# Mic_to_Pi_Entire_design.net
KiCad netlist of a schematic drawn in EAGLE
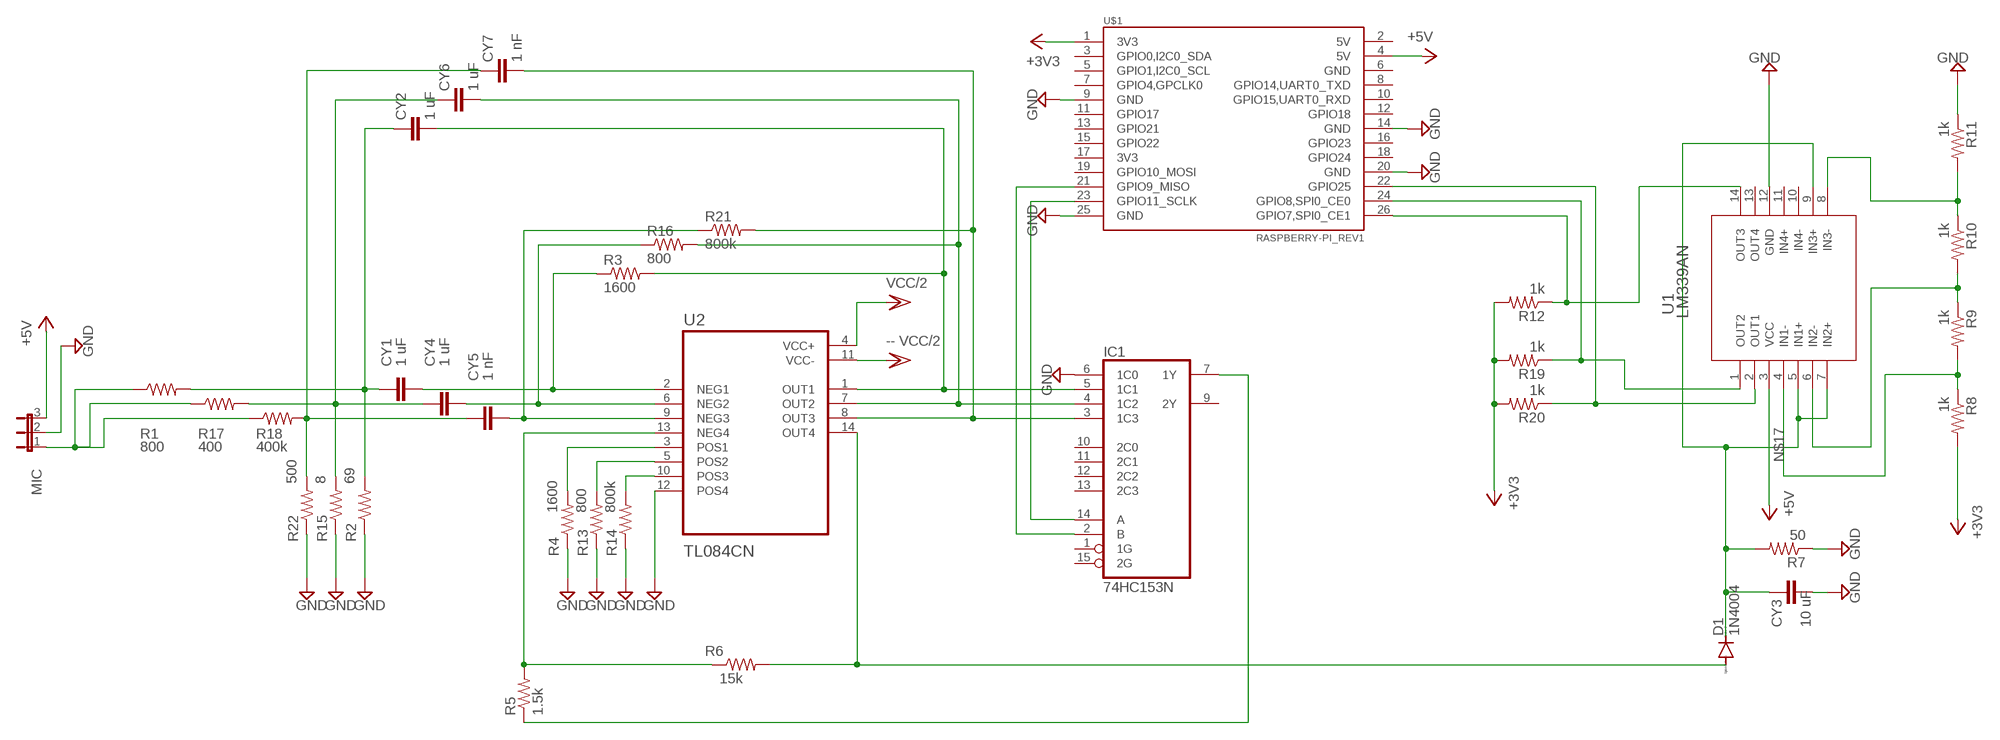
[diagram p0: schematic, sheet 1]

(export (version "E")
  (design (tool "Eeschema 10.0.6"))
  (components
    (comp (ref "CY1")
      (value "1 uF")
      (footprint "eagle-import:YC7B5")
      (libsource (lib "eagle-import") (part "CYYC7B5"))
    )
    (comp (ref "CY2")
      (value "1 uF")
      (footprint "eagle-import:YC7B5")
      (libsource (lib "eagle-import") (part "CYYC7B5"))
    )
    (comp (ref "CY3")
      (value "10 uF")
      (footprint "eagle-import:YC7B5")
      (libsource (lib "eagle-import") (part "CYYC7B5"))
    )
    (comp (ref "CY4")
      (value "1 uF")
      (footprint "eagle-import:YC7B5")
      (libsource (lib "eagle-import") (part "CYYC7B5"))
    )
    (comp (ref "CY5")
      (value "1 nF")
      (footprint "eagle-import:YC7B5")
      (libsource (lib "eagle-import") (part "CYYC7B5"))
    )
    (comp (ref "CY6")
      (value "1 uF")
      (footprint "eagle-import:YC7B5")
      (libsource (lib "eagle-import") (part "CYYC7B5"))
    )
    (comp (ref "CY7")
      (value "1 nF")
      (footprint "eagle-import:YC7B5")
      (libsource (lib "eagle-import") (part "CYYC7B5"))
    )
    (comp (ref "D1")
      (value "1N4004")
      (footprint "eagle-import:DO41-10")
      (libsource (lib "eagle-import") (part "1N4004"))
    )
    (comp (ref "IC1")
      (value "74HC153N")
      (footprint "eagle-import:DIL16")
      (libsource (lib "eagle-import") (part "74153NHC"))
    )
    (comp (ref "MIC")
      (value "JP2W")
      (footprint "eagle-import:JP2W")
      (libsource (lib "eagle-import") (part "JP2W"))
    )
    (comp (ref "R1")
      (value "800")
      (footprint "eagle-import:0204_7")
      (libsource (lib "eagle-import") (part "R-US_0204/7"))
    )
    (comp (ref "R2")
      (value "69")
      (footprint "eagle-import:0204_7")
      (libsource (lib "eagle-import") (part "R-US_0204/7"))
    )
    (comp (ref "R3")
      (value "1600")
      (footprint "eagle-import:0204_7")
      (libsource (lib "eagle-import") (part "R-US_0204/7"))
    )
    (comp (ref "R4")
      (value "1600")
      (footprint "eagle-import:0204_7")
      (libsource (lib "eagle-import") (part "R-US_0204/7"))
    )
    (comp (ref "R5")
      (value "1.5k")
      (footprint "eagle-import:0204_7")
      (libsource (lib "eagle-import") (part "R-US_0204/7"))
    )
    (comp (ref "R6")
      (value "15k")
      (footprint "eagle-import:0204_7")
      (libsource (lib "eagle-import") (part "R-US_0204/7"))
    )
    (comp (ref "R7")
      (value "50")
      (footprint "eagle-import:0204_7")
      (libsource (lib "eagle-import") (part "R-US_0204/7"))
    )
    (comp (ref "R8")
      (value "1k")
      (footprint "eagle-import:0204_7")
      (libsource (lib "eagle-import") (part "R-US_0204/7"))
    )
    (comp (ref "R9")
      (value "1k")
      (footprint "eagle-import:0207_2V")
      (libsource (lib "eagle-import") (part "R-US_0207/2V"))
    )
    (comp (ref "R10")
      (value "1k")
      (footprint "eagle-import:0207_2V")
      (libsource (lib "eagle-import") (part "R-US_0207/2V"))
    )
    (comp (ref "R11")
      (value "1k")
      (footprint "eagle-import:0207_2V")
      (libsource (lib "eagle-import") (part "R-US_0207/2V"))
    )
    (comp (ref "R12")
      (value "1k")
      (footprint "eagle-import:0207_2V")
      (libsource (lib "eagle-import") (part "R-US_0207/2V"))
    )
    (comp (ref "R13")
      (value "800")
      (footprint "eagle-import:0204_7")
      (libsource (lib "eagle-import") (part "R-US_0204/7"))
    )
    (comp (ref "R14")
      (value "800k")
      (footprint "eagle-import:0204_7")
      (libsource (lib "eagle-import") (part "R-US_0204/7"))
    )
    (comp (ref "R15")
      (value "8")
      (footprint "eagle-import:0204_7")
      (libsource (lib "eagle-import") (part "R-US_0204/7"))
    )
    (comp (ref "R16")
      (value "800")
      (footprint "eagle-import:0204_7")
      (libsource (lib "eagle-import") (part "R-US_0204/7"))
    )
    (comp (ref "R17")
      (value "400")
      (footprint "eagle-import:0204_7")
      (libsource (lib "eagle-import") (part "R-US_0204/7"))
    )
    (comp (ref "R18")
      (value "400k")
      (footprint "eagle-import:0204_7")
      (libsource (lib "eagle-import") (part "R-US_0204/7"))
    )
    (comp (ref "R19")
      (value "1k")
      (footprint "eagle-import:0204_7")
      (libsource (lib "eagle-import") (part "R-US_0204/7"))
    )
    (comp (ref "R20")
      (value "1k")
      (footprint "eagle-import:0204_7")
      (libsource (lib "eagle-import") (part "R-US_0204/7"))
    )
    (comp (ref "R21")
      (value "800k")
      (footprint "eagle-import:0204_7")
      (libsource (lib "eagle-import") (part "R-US_0204/7"))
    )
    (comp (ref "R22")
      (value "500")
      (footprint "eagle-import:0204_7")
      (libsource (lib "eagle-import") (part "R-US_0204/7"))
    )
    (comp (ref "U$1")
      (value "RASPBERRY-PI_REV1")
      (footprint "eagle-import:RASPBERRY-PI_REV1")
      (libsource (lib "eagle-import") (part "RASPBERRY-PI_REV1"))
    )
    (comp (ref "U1")
      (value "LM339AN")
      (footprint "eagle-import:PDIP14_646-06_ONS")
      (fields (field (name "COPYRIGHT") "Copyright (C) 2022 Ultra Librarian. All rights reserved."))
      (libsource (lib "eagle-import") (part "LM339AN"))
    )
    (comp (ref "U2")
      (value "TL084CN")
      (footprint "eagle-import:DIP794W45P254L1969H508Q14")
      (fields (field (name "DIGI-KEY_PART_NUMBER") "296-1784-5-ND") (field (name "MF") "Texas Instruments"))
      (libsource (lib "eagle-import") (part "TL084CN"))
    )
  )
  (nets
    (net (code "1") (name "+3V3") (class "Default")
      (node (ref "R12") (pin "2") (pinfunction "2_2") (pintype "passive"))
      (node (ref "R19") (pin "2") (pinfunction "2_2") (pintype "passive"))
      (node (ref "R20") (pin "2") (pinfunction "2_2") (pintype "passive"))
      (node (ref "R8") (pin "2") (pinfunction "2_2") (pintype "passive"))
      (node (ref "U$1") (pin "1") (pinfunction "3V3_1") (pintype "bidirectional"))
    )
    (net (code "2") (name "+5V") (class "Default")
      (node (ref "MIC") (pin "3") (pinfunction "3_3") (pintype "passive"))
      (node (ref "U$1") (pin "4") (pinfunction "5V_4") (pintype "bidirectional"))
      (node (ref "U1") (pin "3") (pinfunction "VCC_3") (pintype "power_in"))
    )
    (net (code "3") (name "-- VCC{slash}2") (class "Default")
      (node (ref "U2") (pin "11") (pinfunction "VCC-_11") (pintype "power_in"))
      (node (ref "U2") (pin "4") (pinfunction "VCC+_4") (pintype "power_in"))
    )
    (net (code "4") (name "/N$17") (class "Default")
      (node (ref "R8") (pin "1") (pinfunction "1_1") (pintype "passive"))
      (node (ref "R9") (pin "2") (pinfunction "2_2") (pintype "passive"))
      (node (ref "U1") (pin "4") (pinfunction "IN1-_4") (pintype "input"))
    )
    (net (code "5") (name "GND") (class "Default")
      (node (ref "CY3") (pin "2") (pinfunction "2_2") (pintype "passive"))
      (node (ref "IC1") (pin "6") (pinfunction "1C0_6") (pintype "input"))
      (node (ref "MIC") (pin "2") (pinfunction "2_2") (pintype "passive"))
      (node (ref "R11") (pin "1") (pinfunction "1_1") (pintype "passive"))
      (node (ref "R13") (pin "1") (pinfunction "1_1") (pintype "passive"))
      (node (ref "R14") (pin "1") (pinfunction "1_1") (pintype "passive"))
      (node (ref "R15") (pin "1") (pinfunction "1_1") (pintype "passive"))
      (node (ref "R2") (pin "1") (pinfunction "1_1") (pintype "passive"))
      (node (ref "R22") (pin "1") (pinfunction "1_1") (pintype "passive"))
      (node (ref "R4") (pin "1") (pinfunction "1_1") (pintype "passive"))
      (node (ref "R7") (pin "1") (pinfunction "1_1") (pintype "passive"))
      (node (ref "U$1") (pin "14") (pinfunction "GND_14") (pintype "bidirectional"))
      (node (ref "U$1") (pin "20") (pinfunction "GND_20") (pintype "bidirectional"))
      (node (ref "U$1") (pin "25") (pinfunction "GND_25") (pintype "bidirectional"))
      (node (ref "U$1") (pin "9") (pinfunction "GND_9") (pintype "bidirectional"))
      (node (ref "U1") (pin "12") (pinfunction "GND_12") (pintype "passive"))
      (node (ref "U2") (pin "12") (pinfunction "POS4_12") (pintype "input"))
    )
    (net (code "6") (name "Net-(CY1-Pad1)") (class "Default")
      (node (ref "CY1") (pin "1") (pinfunction "1_1") (pintype "passive"))
      (node (ref "CY2") (pin "1") (pinfunction "1_1") (pintype "passive"))
      (node (ref "R1") (pin "2") (pinfunction "2_2") (pintype "passive"))
      (node (ref "R2") (pin "2") (pinfunction "2_2") (pintype "passive"))
    )
    (net (code "7") (name "Net-(CY4-Pad1)") (class "Default")
      (node (ref "CY4") (pin "1") (pinfunction "1_1") (pintype "passive"))
      (node (ref "CY6") (pin "1") (pinfunction "1_1") (pintype "passive"))
      (node (ref "R15") (pin "2") (pinfunction "2_2") (pintype "passive"))
      (node (ref "R17") (pin "2") (pinfunction "2_2") (pintype "passive"))
    )
    (net (code "8") (name "Net-(CY5-Pad1)") (class "Default")
      (node (ref "CY5") (pin "1") (pinfunction "1_1") (pintype "passive"))
      (node (ref "CY7") (pin "1") (pinfunction "1_1") (pintype "passive"))
      (node (ref "R18") (pin "2") (pinfunction "2_2") (pintype "passive"))
      (node (ref "R22") (pin "2") (pinfunction "2_2") (pintype "passive"))
    )
    (net (code "9") (name "Net-(IC1A-1C1)") (class "Default")
      (node (ref "CY2") (pin "2") (pinfunction "2_2") (pintype "passive"))
      (node (ref "IC1") (pin "5") (pinfunction "1C1_5") (pintype "input"))
      (node (ref "R3") (pin "2") (pinfunction "2_2") (pintype "passive"))
      (node (ref "U2") (pin "1") (pinfunction "OUT1_1") (pintype "output"))
    )
    (net (code "10") (name "Net-(IC1A-1C2)") (class "Default")
      (node (ref "CY6") (pin "2") (pinfunction "2_2") (pintype "passive"))
      (node (ref "IC1") (pin "4") (pinfunction "1C2_4") (pintype "input"))
      (node (ref "R16") (pin "2") (pinfunction "2_2") (pintype "passive"))
      (node (ref "U2") (pin "7") (pinfunction "OUT2_7") (pintype "output"))
    )
    (net (code "11") (name "Net-(IC1A-1C3)") (class "Default")
      (node (ref "CY7") (pin "2") (pinfunction "2_2") (pintype "passive"))
      (node (ref "IC1") (pin "3") (pinfunction "1C3_3") (pintype "input"))
      (node (ref "R21") (pin "2") (pinfunction "2_2") (pintype "passive"))
      (node (ref "U2") (pin "8") (pinfunction "OUT3_8") (pintype "output"))
    )
    (net (code "12") (name "Net-(IC1A-1Y)") (class "Default")
      (node (ref "IC1") (pin "7") (pinfunction "1Y_7") (pintype "output"))
      (node (ref "R5") (pin "1") (pinfunction "1_1") (pintype "passive"))
    )
    (net (code "13") (name "Net-(IC1A-A)") (class "Default")
      (node (ref "IC1") (pin "14") (pinfunction "A_14") (pintype "input"))
      (node (ref "U$1") (pin "23") (pinfunction "GPIO11_SCLK_23") (pintype "bidirectional"))
    )
    (net (code "14") (name "Net-(IC1A-B)") (class "Default")
      (node (ref "IC1") (pin "2") (pinfunction "B_2") (pintype "input"))
      (node (ref "U$1") (pin "21") (pinfunction "GPIO9_MISO_21") (pintype "bidirectional"))
    )
    (net (code "15") (name "Net-(MIC-Pad1)") (class "Default")
      (node (ref "MIC") (pin "1") (pinfunction "1_1") (pintype "passive"))
      (node (ref "R1") (pin "1") (pinfunction "1_1") (pintype "passive"))
      (node (ref "R17") (pin "1") (pinfunction "1_1") (pintype "passive"))
      (node (ref "R18") (pin "1") (pinfunction "1_1") (pintype "passive"))
    )
    (net (code "16") (name "Net-(U$1-GPIO7,SPI0_CE1)") (class "Default")
      (node (ref "R12") (pin "1") (pinfunction "1_1") (pintype "passive"))
      (node (ref "U$1") (pin "26") (pinfunction "GPIO7,SPI0_CE1_26") (pintype "bidirectional"))
      (node (ref "U1") (pin "14") (pinfunction "OUT3_14") (pintype "output"))
    )
    (net (code "17") (name "Net-(U$1-GPIO8,SPI0_CE0)") (class "Default")
      (node (ref "R19") (pin "1") (pinfunction "1_1") (pintype "passive"))
      (node (ref "U$1") (pin "24") (pinfunction "GPIO8,SPI0_CE0_24") (pintype "bidirectional"))
      (node (ref "U1") (pin "1") (pinfunction "OUT2_1") (pintype "output"))
    )
    (net (code "18") (name "Net-(U$1-GPIO25)") (class "Default")
      (node (ref "R20") (pin "1") (pinfunction "1_1") (pintype "passive"))
      (node (ref "U$1") (pin "22") (pinfunction "GPIO25_22") (pintype "bidirectional"))
      (node (ref "U1") (pin "2") (pinfunction "OUT1_2") (pintype "output"))
    )
    (net (code "19") (name "Net-(U1-IN1+)") (class "Default")
      (node (ref "CY3") (pin "1") (pinfunction "1_1") (pintype "passive"))
      (node (ref "D1") (pin "C") (pinfunction "C_C") (pintype "passive"))
      (node (ref "R7") (pin "2") (pinfunction "2_2") (pintype "passive"))
      (node (ref "U1") (pin "5") (pinfunction "IN1+_5") (pintype "input"))
      (node (ref "U1") (pin "7") (pinfunction "IN2+_7") (pintype "input"))
      (node (ref "U1") (pin "9") (pinfunction "IN3+_9") (pintype "input"))
    )
    (net (code "20") (name "Net-(U1-IN2-)") (class "Default")
      (node (ref "R10") (pin "2") (pinfunction "2_2") (pintype "passive"))
      (node (ref "R9") (pin "1") (pinfunction "1_1") (pintype "passive"))
      (node (ref "U1") (pin "6") (pinfunction "IN2-_6") (pintype "input"))
    )
    (net (code "21") (name "Net-(U1-IN3-)") (class "Default")
      (node (ref "R10") (pin "1") (pinfunction "1_1") (pintype "passive"))
      (node (ref "R11") (pin "2") (pinfunction "2_2") (pintype "passive"))
      (node (ref "U1") (pin "8") (pinfunction "IN3-_8") (pintype "input"))
    )
    (net (code "22") (name "Net-(U2-NEG1)") (class "Default")
      (node (ref "CY1") (pin "2") (pinfunction "2_2") (pintype "passive"))
      (node (ref "R3") (pin "1") (pinfunction "1_1") (pintype "passive"))
      (node (ref "U2") (pin "2") (pinfunction "NEG1_2") (pintype "input"))
    )
    (net (code "23") (name "Net-(U2-NEG2)") (class "Default")
      (node (ref "CY4") (pin "2") (pinfunction "2_2") (pintype "passive"))
      (node (ref "R16") (pin "1") (pinfunction "1_1") (pintype "passive"))
      (node (ref "U2") (pin "6") (pinfunction "NEG2_6") (pintype "input"))
    )
    (net (code "24") (name "Net-(U2-NEG3)") (class "Default")
      (node (ref "CY5") (pin "2") (pinfunction "2_2") (pintype "passive"))
      (node (ref "R21") (pin "1") (pinfunction "1_1") (pintype "passive"))
      (node (ref "U2") (pin "9") (pinfunction "NEG3_9") (pintype "input"))
    )
    (net (code "25") (name "Net-(U2-NEG4)") (class "Default")
      (node (ref "R5") (pin "2") (pinfunction "2_2") (pintype "passive"))
      (node (ref "R6") (pin "1") (pinfunction "1_1") (pintype "passive"))
      (node (ref "U2") (pin "13") (pinfunction "NEG4_13") (pintype "input"))
    )
    (net (code "26") (name "Net-(U2-OUT4)") (class "Default")
      (node (ref "D1") (pin "A") (pinfunction "A_A") (pintype "passive"))
      (node (ref "R6") (pin "2") (pinfunction "2_2") (pintype "passive"))
      (node (ref "U2") (pin "14") (pinfunction "OUT4_14") (pintype "output"))
    )
    (net (code "27") (name "Net-(U2-POS1)") (class "Default")
      (node (ref "R4") (pin "2") (pinfunction "2_2") (pintype "passive"))
      (node (ref "U2") (pin "3") (pinfunction "POS1_3") (pintype "input"))
    )
    (net (code "28") (name "Net-(U2-POS2)") (class "Default")
      (node (ref "R13") (pin "2") (pinfunction "2_2") (pintype "passive"))
      (node (ref "U2") (pin "5") (pinfunction "POS2_5") (pintype "input"))
    )
    (net (code "29") (name "Net-(U2-POS3)") (class "Default")
      (node (ref "R14") (pin "2") (pinfunction "2_2") (pintype "passive"))
      (node (ref "U2") (pin "10") (pinfunction "POS3_10") (pintype "input"))
    )
    (net (code "30") (name "unconnected-(IC1A-1G-Pad1)") (class "Default")
      (node (ref "IC1") (pin "1") (pinfunction "1G_1") (pintype "input"))
    )
    (net (code "31") (name "unconnected-(IC1A-2C0-Pad10)") (class "Default")
      (node (ref "IC1") (pin "10") (pinfunction "2C0_10") (pintype "input"))
    )
    (net (code "32") (name "unconnected-(IC1A-2C1-Pad11)") (class "Default")
      (node (ref "IC1") (pin "11") (pinfunction "2C1_11") (pintype "input"))
    )
    (net (code "33") (name "unconnected-(IC1A-2C2-Pad12)") (class "Default")
      (node (ref "IC1") (pin "12") (pinfunction "2C2_12") (pintype "input"))
    )
    (net (code "34") (name "unconnected-(IC1A-2C3-Pad13)") (class "Default")
      (node (ref "IC1") (pin "13") (pinfunction "2C3_13") (pintype "input"))
    )
    (net (code "35") (name "unconnected-(IC1A-2G-Pad15)") (class "Default")
      (node (ref "IC1") (pin "15") (pinfunction "2G_15") (pintype "input"))
    )
    (net (code "36") (name "unconnected-(IC1A-2Y-Pad9)") (class "Default")
      (node (ref "IC1") (pin "9") (pinfunction "2Y_9") (pintype "output"))
    )
    (net (code "37") (name "unconnected-(U$1-3V3-Pad17)") (class "Default")
      (node (ref "U$1") (pin "17") (pinfunction "3V3_17") (pintype "bidirectional"))
    )
    (net (code "38") (name "unconnected-(U$1-5V-Pad2)") (class "Default")
      (node (ref "U$1") (pin "2") (pinfunction "5V_2") (pintype "bidirectional"))
    )
    (net (code "39") (name "unconnected-(U$1-GND-Pad6)") (class "Default")
      (node (ref "U$1") (pin "6") (pinfunction "GND_6") (pintype "bidirectional"))
    )
    (net (code "40") (name "unconnected-(U$1-GPIO0,I2C0_SDA-Pad3)") (class "Default")
      (node (ref "U$1") (pin "3") (pinfunction "GPIO0,I2C0_SDA_3") (pintype "bidirectional"))
    )
    (net (code "41") (name "unconnected-(U$1-GPIO1,I2C0_SCL-Pad5)") (class "Default")
      (node (ref "U$1") (pin "5") (pinfunction "GPIO1,I2C0_SCL_5") (pintype "bidirectional"))
    )
    (net (code "42") (name "unconnected-(U$1-GPIO4,GPCLK0-Pad7)") (class "Default")
      (node (ref "U$1") (pin "7") (pinfunction "GPIO4,GPCLK0_7") (pintype "bidirectional"))
    )
    (net (code "43") (name "unconnected-(U$1-GPIO10_MOSI-Pad19)") (class "Default")
      (node (ref "U$1") (pin "19") (pinfunction "GPIO10_MOSI_19") (pintype "bidirectional"))
    )
    (net (code "44") (name "unconnected-(U$1-GPIO14,UART0_TXD-Pad8)") (class "Default")
      (node (ref "U$1") (pin "8") (pinfunction "GPIO14,UART0_TXD_8") (pintype "bidirectional"))
    )
    (net (code "45") (name "unconnected-(U$1-GPIO15,UART0_RXD-Pad10)") (class "Default")
      (node (ref "U$1") (pin "10") (pinfunction "GPIO15,UART0_RXD_10") (pintype "bidirectional"))
    )
    (net (code "46") (name "unconnected-(U$1-GPIO17-Pad11)") (class "Default")
      (node (ref "U$1") (pin "11") (pinfunction "GPIO17_11") (pintype "bidirectional"))
    )
    (net (code "47") (name "unconnected-(U$1-GPIO18-Pad12)") (class "Default")
      (node (ref "U$1") (pin "12") (pinfunction "GPIO18_12") (pintype "bidirectional"))
    )
    (net (code "48") (name "unconnected-(U$1-GPIO21-Pad13)") (class "Default")
      (node (ref "U$1") (pin "13") (pinfunction "GPIO21_13") (pintype "bidirectional"))
    )
    (net (code "49") (name "unconnected-(U$1-GPIO22-Pad15)") (class "Default")
      (node (ref "U$1") (pin "15") (pinfunction "GPIO22_15") (pintype "bidirectional"))
    )
    (net (code "50") (name "unconnected-(U$1-GPIO23-Pad16)") (class "Default")
      (node (ref "U$1") (pin "16") (pinfunction "GPIO23_16") (pintype "bidirectional"))
    )
    (net (code "51") (name "unconnected-(U$1-GPIO24-Pad18)") (class "Default")
      (node (ref "U$1") (pin "18") (pinfunction "GPIO24_18") (pintype "bidirectional"))
    )
    (net (code "52") (name "unconnected-(U1-IN4+-Pad11)") (class "Default")
      (node (ref "U1") (pin "11") (pinfunction "IN4+_11") (pintype "input"))
    )
    (net (code "53") (name "unconnected-(U1-IN4--Pad10)") (class "Default")
      (node (ref "U1") (pin "10") (pinfunction "IN4-_10") (pintype "input"))
    )
    (net (code "54") (name "unconnected-(U1-OUT4-Pad13)") (class "Default")
      (node (ref "U1") (pin "13") (pinfunction "OUT4_13") (pintype "output"))
    )
  )
)
